# SFT_MainBoard1_0v.net
KiCad netlist of a schematic drawn in EAGLE
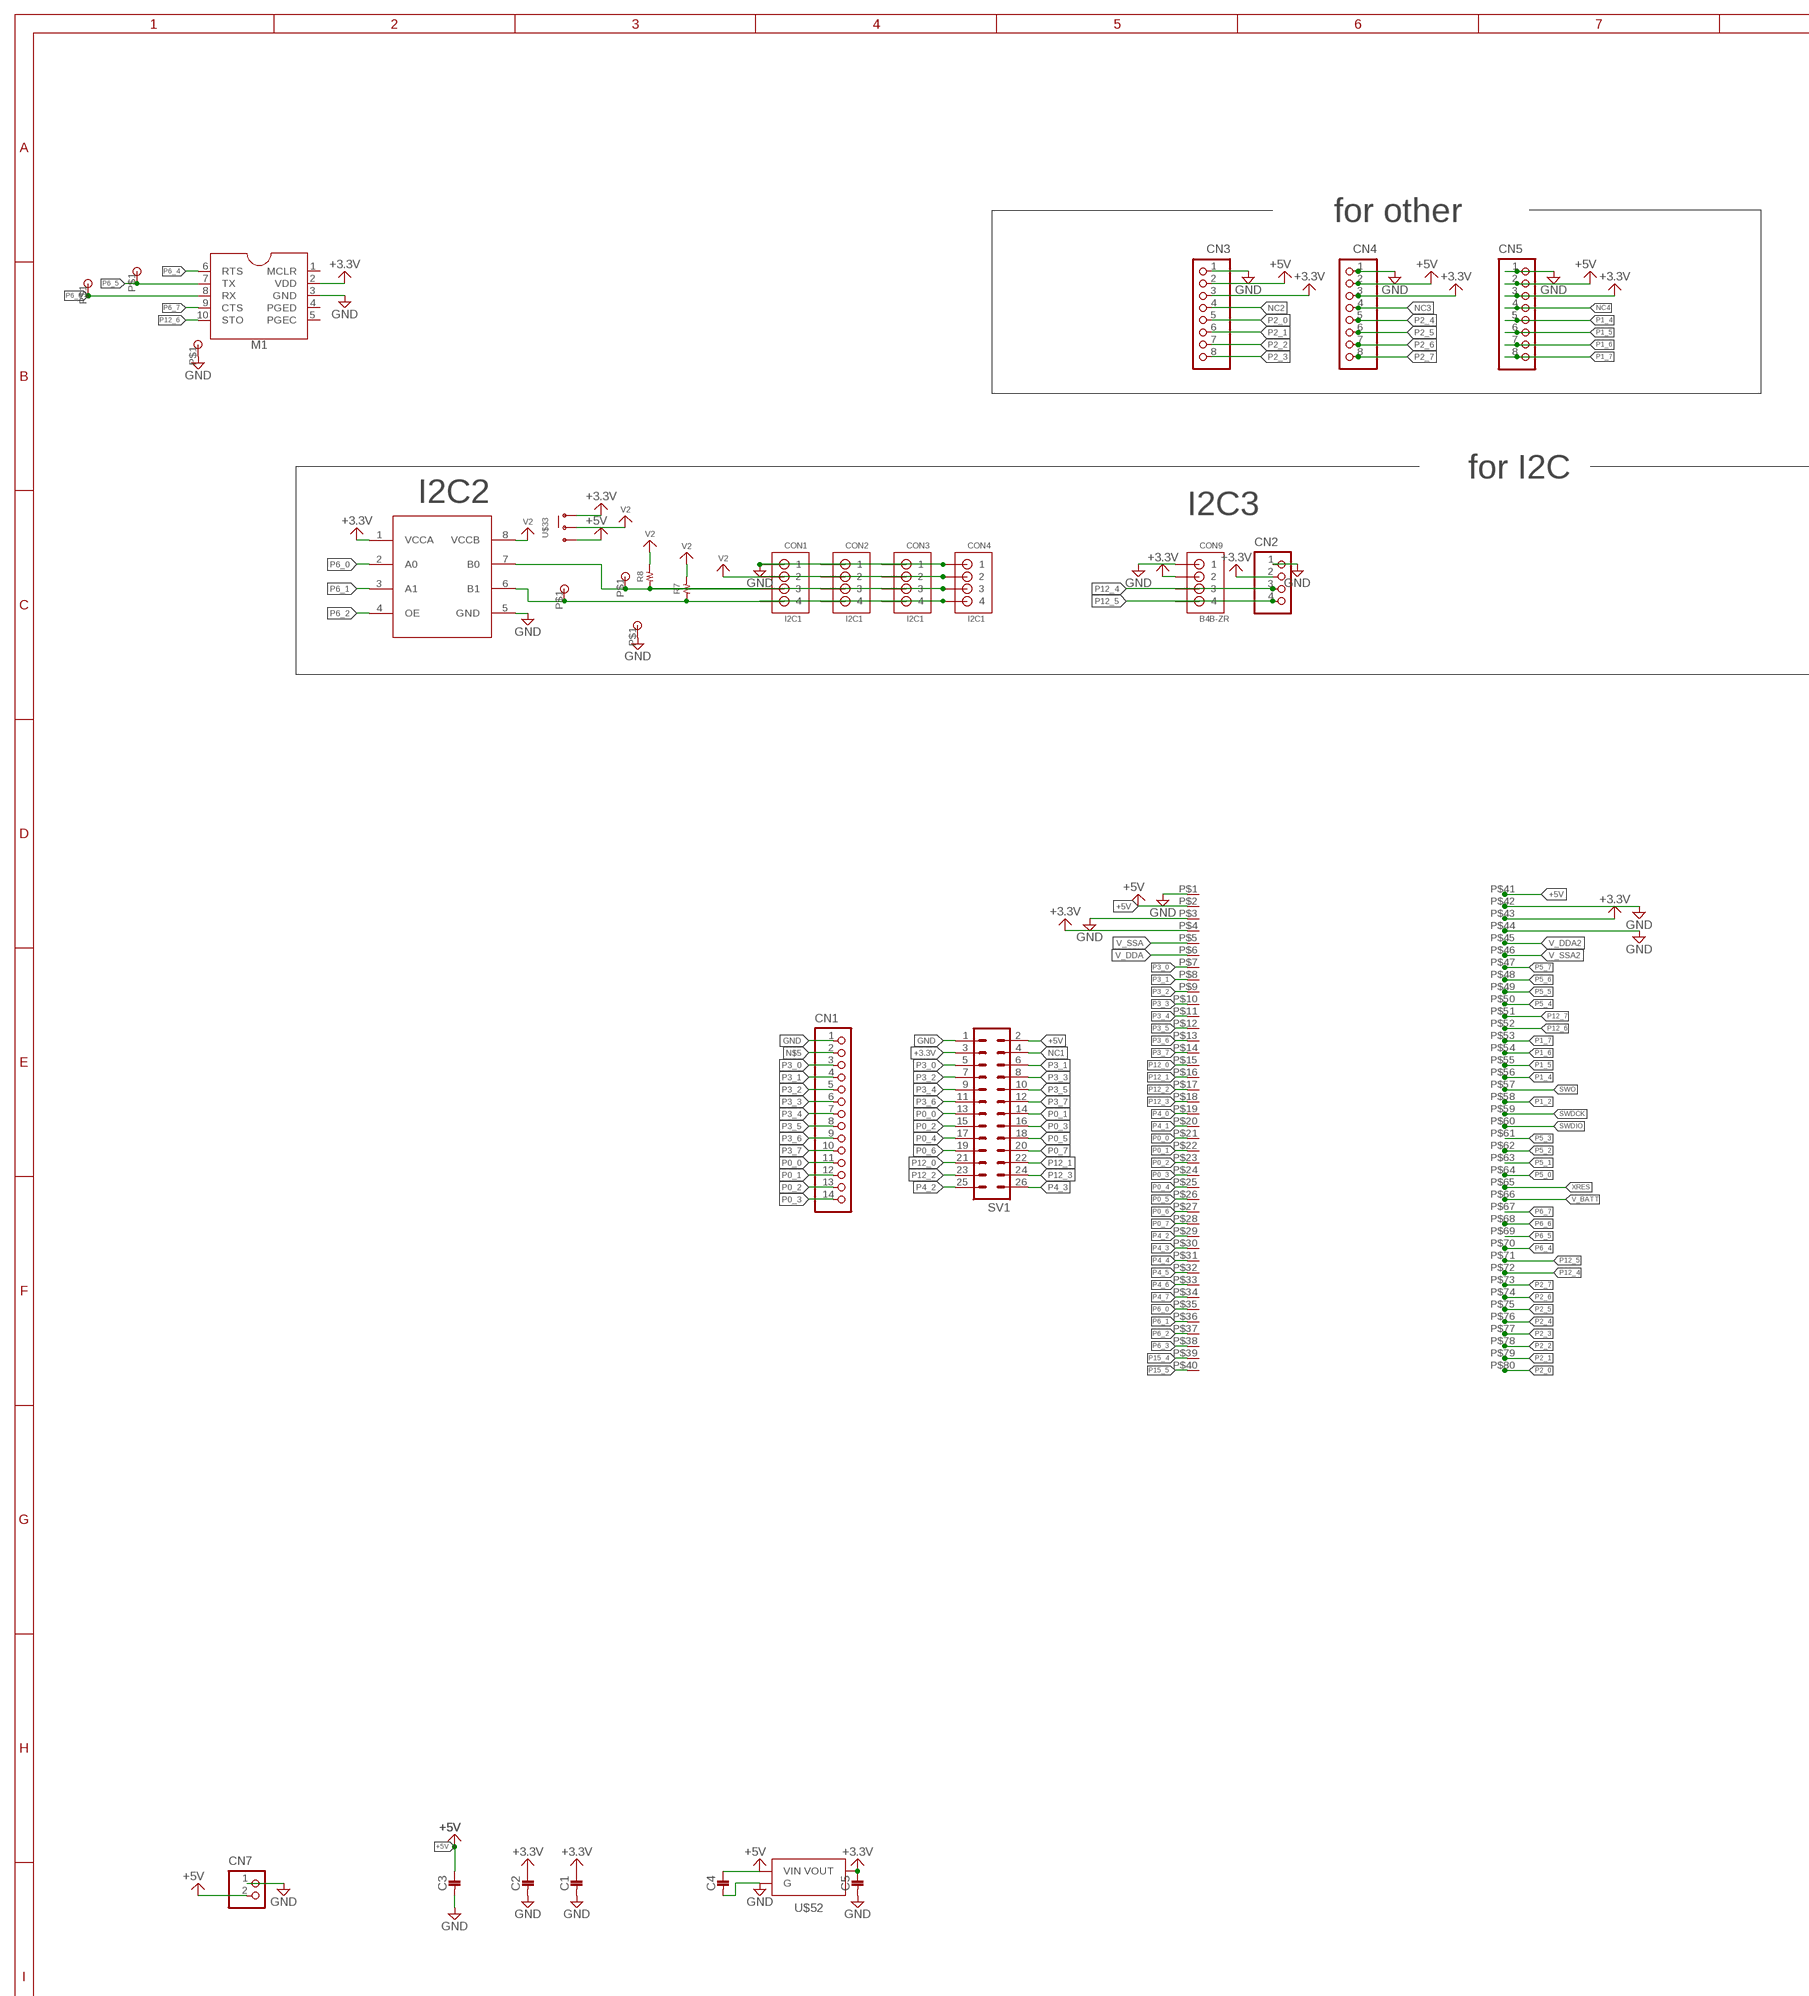
[diagram p0: schematic, sheet 1, part 1 of 2]
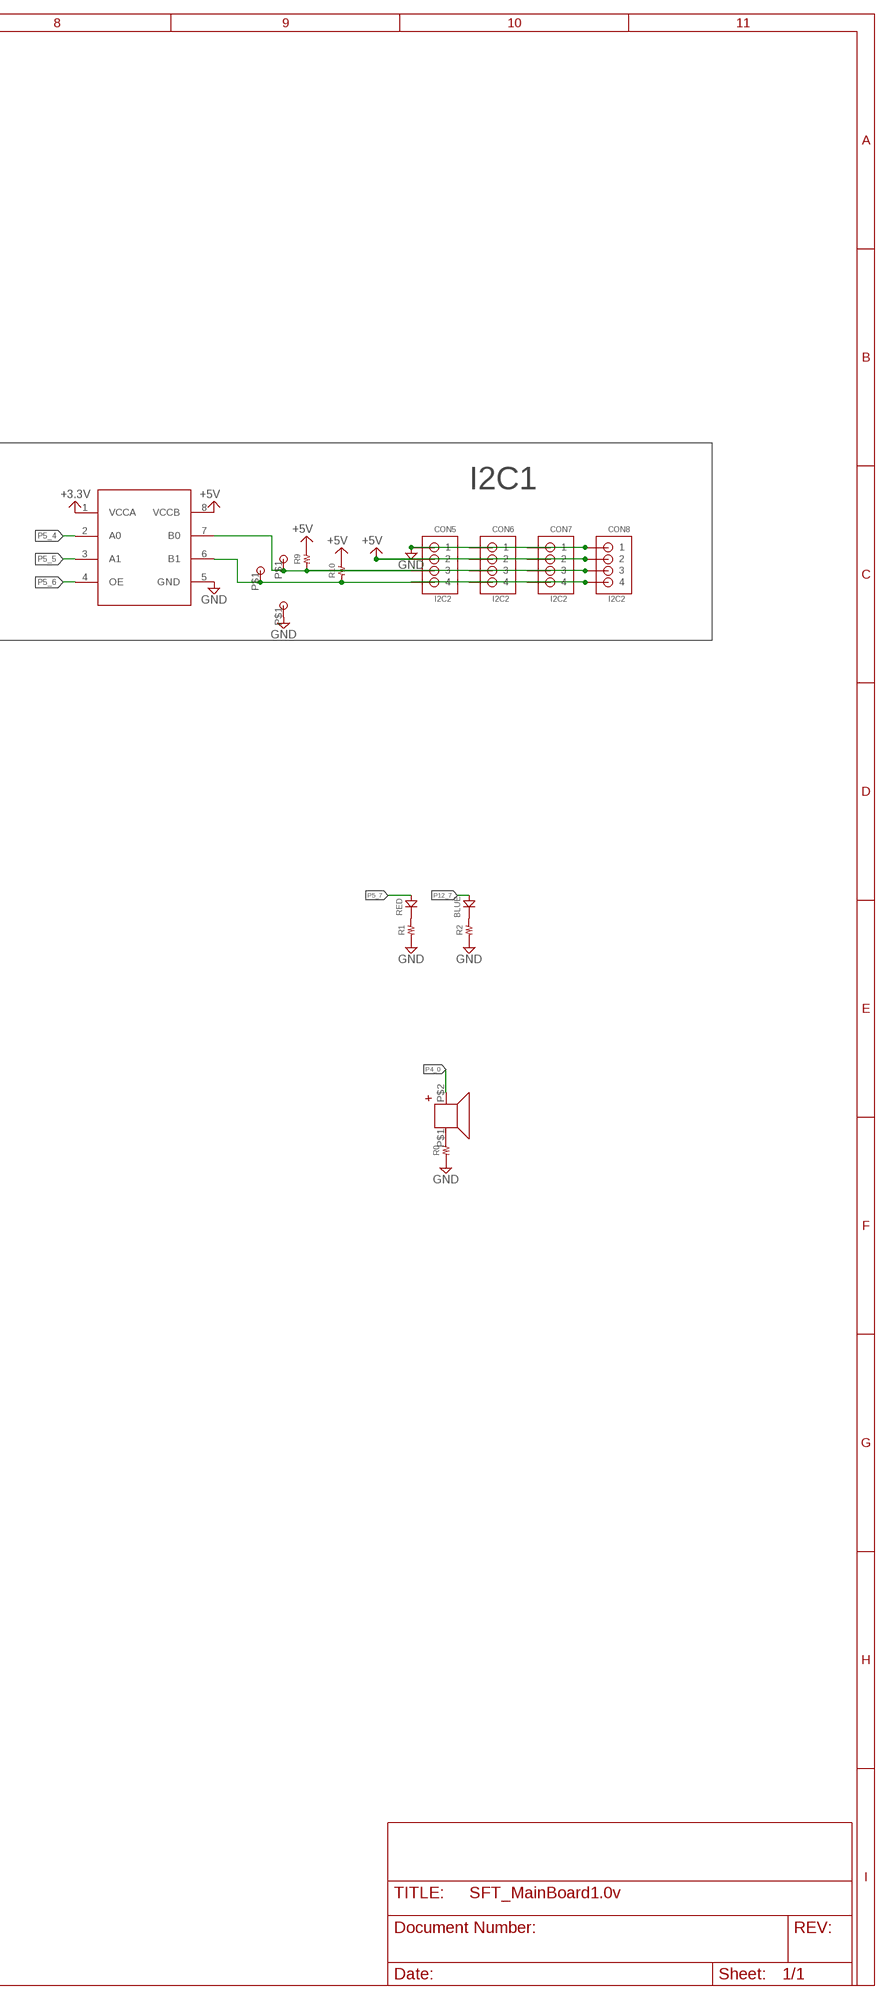
[diagram p1: schematic, sheet 1, part 2 of 2]

(export (version "E")
  (design (tool "Eeschema 10.0.6"))
  (components
    (comp (ref "BLUE")
      (value "CHIPLED")
      (footprint "eagle-import:1608")
      (libsource (lib "eagle-import") (part "CHIPLED"))
    )
    (comp (ref "C1")
      (value "1608")
      (footprint "eagle-import:1608")
      (libsource (lib "eagle-import") (part "1608"))
    )
    (comp (ref "C2")
      (value "1608")
      (footprint "eagle-import:1608")
      (libsource (lib "eagle-import") (part "1608"))
    )
    (comp (ref "C3")
      (value "1608")
      (footprint "eagle-import:1608")
      (libsource (lib "eagle-import") (part "1608"))
    )
    (comp (ref "C4")
      (value "1608")
      (footprint "eagle-import:1608")
      (libsource (lib "eagle-import") (part "1608"))
    )
    (comp (ref "C5")
      (value "1608")
      (footprint "eagle-import:1608")
      (libsource (lib "eagle-import") (part "1608"))
    )
    (comp (ref "CN1")
      (value "B14B-XASK-1")
      (footprint "eagle-import:B14B-XASK-1")
      (libsource (lib "eagle-import") (part "B14B-XASK-1"))
    )
    (comp (ref "CN2")
      (value "B4B-PH-K-S")
      (footprint "eagle-import:B4B-PH-K-S")
      (libsource (lib "eagle-import") (part "B4B-PH-K-S"))
    )
    (comp (ref "CN3")
      (value "B8B-PH-K-S")
      (footprint "eagle-import:B8B-PH-K-S")
      (libsource (lib "eagle-import") (part "B8B-PH-K-S"))
    )
    (comp (ref "CN4")
      (value "B8B-PH-K-S")
      (footprint "eagle-import:B8B-PH-K-S")
      (libsource (lib "eagle-import") (part "B8B-PH-K-S"))
    )
    (comp (ref "CN5")
      (value "B8B-PH-K-S")
      (footprint "eagle-import:B8B-PH-K-S")
      (libsource (lib "eagle-import") (part "B8B-PH-K-S"))
    )
    (comp (ref "CN7")
      (value "B2B-PH-K-S")
      (footprint "eagle-import:B2B-PH-K-S")
      (libsource (lib "eagle-import") (part "B2B-PH-K-S"))
    )
    (comp (ref "CON1")
      (value "I2C1")
      (footprint "eagle-import:B4B-ZR")
      (libsource (lib "eagle-import") (part "B4B-ZR"))
    )
    (comp (ref "CON2")
      (value "I2C1")
      (footprint "eagle-import:B4B-ZR")
      (libsource (lib "eagle-import") (part "B4B-ZR"))
    )
    (comp (ref "CON3")
      (value "I2C1")
      (footprint "eagle-import:B4B-ZR")
      (libsource (lib "eagle-import") (part "B4B-ZR"))
    )
    (comp (ref "CON4")
      (value "I2C1")
      (footprint "eagle-import:B4B-ZR")
      (libsource (lib "eagle-import") (part "B4B-ZR"))
    )
    (comp (ref "CON5")
      (value "I2C2")
      (footprint "eagle-import:B4B-ZR")
      (libsource (lib "eagle-import") (part "B4B-ZR"))
    )
    (comp (ref "CON6")
      (value "I2C2")
      (footprint "eagle-import:B4B-ZR")
      (libsource (lib "eagle-import") (part "B4B-ZR"))
    )
    (comp (ref "CON7")
      (value "I2C2")
      (footprint "eagle-import:B4B-ZR")
      (libsource (lib "eagle-import") (part "B4B-ZR"))
    )
    (comp (ref "CON8")
      (value "I2C2")
      (footprint "eagle-import:B4B-ZR")
      (libsource (lib "eagle-import") (part "B4B-ZR"))
    )
    (comp (ref "CON9")
      (value "B4B-ZR")
      (footprint "eagle-import:B4B-ZR")
      (libsource (lib "eagle-import") (part "B4B-ZR"))
    )
    (comp (ref "IC1")
      (value "I2C_FXMA2102")
      (footprint "eagle-import:DIL08")
      (libsource (lib "eagle-import") (part "I2C_FXMA2102"))
    )
    (comp (ref "IC2")
      (value "I2C_FXMA2102")
      (footprint "eagle-import:DIL08")
      (libsource (lib "eagle-import") (part "I2C_FXMA2102"))
    )
    (comp (ref "M1")
      (value "SBDBT")
      (footprint "eagle-import:DIL10")
      (libsource (lib "eagle-import") (part "SBDBT"))
    )
    (comp (ref "R0")
      (value "RESISTOR__SMD")
      (footprint "eagle-import:1608")
      (libsource (lib "eagle-import") (part "RESISTOR__SMD"))
    )
    (comp (ref "R1")
      (value "RESISTOR__SMD")
      (footprint "eagle-import:1608")
      (libsource (lib "eagle-import") (part "RESISTOR__SMD"))
    )
    (comp (ref "R2")
      (value "RESISTOR__SMD")
      (footprint "eagle-import:1608")
      (libsource (lib "eagle-import") (part "RESISTOR__SMD"))
    )
    (comp (ref "R7")
      (value "RESISTOR__SMD")
      (footprint "eagle-import:1608")
      (libsource (lib "eagle-import") (part "RESISTOR__SMD"))
    )
    (comp (ref "R8")
      (value "RESISTOR__SMD")
      (footprint "eagle-import:1608")
      (libsource (lib "eagle-import") (part "RESISTOR__SMD"))
    )
    (comp (ref "R9")
      (value "RESISTOR__SMD")
      (footprint "eagle-import:1608")
      (libsource (lib "eagle-import") (part "RESISTOR__SMD"))
    )
    (comp (ref "R10")
      (value "RESISTOR__SMD")
      (footprint "eagle-import:1608")
      (libsource (lib "eagle-import") (part "RESISTOR__SMD"))
    )
    (comp (ref "RED")
      (value "CHIPLED")
      (footprint "eagle-import:1608")
      (libsource (lib "eagle-import") (part "CHIPLED"))
    )
    (comp (ref "SP")
      (value "PKLCS1212E4001")
      (footprint "eagle-import:PKLCS1212E4001")
      (libsource (lib "eagle-import") (part "PKLCS1212E4001"))
    )
    (comp (ref "SV1")
      (value "ML26")
      (footprint "eagle-import:ML26")
      (libsource (lib "eagle-import") (part "ML26"))
    )
    (comp (ref "U$2")
      (value "PSOC_5LP")
      (footprint "eagle-import:PSOC_5LP")
      (libsource (lib "eagle-import") (part "PSOC_5LP"))
    )
    (comp (ref "U$15")
      (value "CHECK_0.8MM")
      (footprint "eagle-import:CHECK_0.8MM")
      (libsource (lib "eagle-import") (part "CHECK_0.8MM"))
    )
    (comp (ref "U$18")
      (value "CHECK_0.8MM")
      (footprint "eagle-import:CHECK_0.8MM")
      (libsource (lib "eagle-import") (part "CHECK_0.8MM"))
    )
    (comp (ref "U$33")
      (value "SS12D01G4")
      (footprint "eagle-import:SS12D01G4")
      (libsource (lib "eagle-import") (part "SS12D01G4"))
    )
    (comp (ref "U$37")
      (value "CHECK_0.8MM")
      (footprint "eagle-import:CHECK_0.8MM")
      (libsource (lib "eagle-import") (part "CHECK_0.8MM"))
    )
    (comp (ref "U$38")
      (value "CHECK_0.8MM")
      (footprint "eagle-import:CHECK_0.8MM")
      (libsource (lib "eagle-import") (part "CHECK_0.8MM"))
    )
    (comp (ref "U$39")
      (value "CHECK_0.8MM")
      (footprint "eagle-import:CHECK_0.8MM")
      (libsource (lib "eagle-import") (part "CHECK_0.8MM"))
    )
    (comp (ref "U$52")
      (value "NJM2845")
      (footprint "eagle-import:TO252")
      (libsource (lib "eagle-import") (part "NJM2845"))
    )
    (comp (ref "U$78")
      (value "CHECK_0.8MM")
      (footprint "eagle-import:CHECK_0.8MM")
      (libsource (lib "eagle-import") (part "CHECK_0.8MM"))
    )
    (comp (ref "U$79")
      (value "CHECK_0.8MM")
      (footprint "eagle-import:CHECK_0.8MM")
      (libsource (lib "eagle-import") (part "CHECK_0.8MM"))
    )
    (comp (ref "U$82")
      (value "CHECK_0.8MM")
      (footprint "eagle-import:CHECK_0.8MM")
      (libsource (lib "eagle-import") (part "CHECK_0.8MM"))
    )
    (comp (ref "U$83")
      (value "CHECK_0.8MM")
      (footprint "eagle-import:CHECK_0.8MM")
      (libsource (lib "eagle-import") (part "CHECK_0.8MM"))
    )
  )
  (nets
    (net (code "1") (name "+3.3V") (class "Default")
      (node (ref "C1") (pin "P$1") (pinfunction "1_P$1") (pintype "passive"))
      (node (ref "C2") (pin "P$1") (pinfunction "1_P$1") (pintype "passive"))
      (node (ref "C5") (pin "P$1") (pinfunction "1_P$1") (pintype "passive"))
      (node (ref "CN2") (pin "2") (pinfunction "2_2") (pintype "passive"))
      (node (ref "CN3") (pin "3") (pinfunction "3_3") (pintype "passive"))
      (node (ref "CN4") (pin "3") (pinfunction "3_3") (pintype "passive"))
      (node (ref "CN5") (pin "3") (pinfunction "3_3") (pintype "passive"))
      (node (ref "CON9") (pin "2") (pinfunction "2_2") (pintype "bidirectional"))
      (node (ref "IC1") (pin "1") (pinfunction "VCCA_1") (pintype "bidirectional"))
      (node (ref "IC2") (pin "1") (pinfunction "VCCA_1") (pintype "bidirectional"))
      (node (ref "M1") (pin "2") (pinfunction "VDD_2") (pintype "passive"))
      (node (ref "SV1") (pin "3") (pinfunction "3_3") (pintype "passive"))
      (node (ref "U$2") (pin "P$4") (pinfunction "P$4_P$4") (pintype "bidirectional"))
      (node (ref "U$2") (pin "P$43") (pinfunction "P$43_P$43") (pintype "bidirectional"))
      (node (ref "U$33") (pin "1") (pinfunction "P$1_1") (pintype "bidirectional"))
      (node (ref "U$52") (pin "3") (pinfunction "VOUT_3") (pintype "power_in"))
    )
    (net (code "2") (name "+5V") (class "Default")
      (node (ref "C3") (pin "P$1") (pinfunction "1_P$1") (pintype "passive"))
      (node (ref "C4") (pin "P$1") (pinfunction "1_P$1") (pintype "passive"))
      (node (ref "CN3") (pin "2") (pinfunction "2_2") (pintype "passive"))
      (node (ref "CN4") (pin "2") (pinfunction "2_2") (pintype "passive"))
      (node (ref "CN5") (pin "2") (pinfunction "2_2") (pintype "passive"))
      (node (ref "CN7") (pin "2") (pinfunction "2_2") (pintype "passive"))
      (node (ref "CON5") (pin "2") (pinfunction "2_2") (pintype "bidirectional"))
      (node (ref "CON6") (pin "2") (pinfunction "2_2") (pintype "bidirectional"))
      (node (ref "CON7") (pin "2") (pinfunction "2_2") (pintype "bidirectional"))
      (node (ref "CON8") (pin "2") (pinfunction "2_2") (pintype "bidirectional"))
      (node (ref "IC1") (pin "8") (pinfunction "VCCB_8") (pintype "bidirectional"))
      (node (ref "R10") (pin "2") (pinfunction "P$2_2") (pintype "passive"))
      (node (ref "R9") (pin "2") (pinfunction "P$2_2") (pintype "passive"))
      (node (ref "SV1") (pin "2") (pinfunction "2_2") (pintype "passive"))
      (node (ref "U$2") (pin "P$2") (pinfunction "P$2_P$2") (pintype "bidirectional"))
      (node (ref "U$2") (pin "P$41") (pinfunction "P$41_P$41") (pintype "bidirectional"))
      (node (ref "U$33") (pin "3") (pinfunction "P$3_3") (pintype "bidirectional"))
      (node (ref "U$52") (pin "1") (pinfunction "VIN_1") (pintype "power_in"))
    )
    (net (code "3") (name "GND") (class "Default")
      (node (ref "C1") (pin "P$2") (pinfunction "2_P$2") (pintype "passive"))
      (node (ref "C2") (pin "P$2") (pinfunction "2_P$2") (pintype "passive"))
      (node (ref "C3") (pin "P$2") (pinfunction "2_P$2") (pintype "passive"))
      (node (ref "C4") (pin "P$2") (pinfunction "2_P$2") (pintype "passive"))
      (node (ref "C5") (pin "P$2") (pinfunction "2_P$2") (pintype "passive"))
      (node (ref "CN1") (pin "1") (pinfunction "1_1") (pintype "passive"))
      (node (ref "CN2") (pin "1") (pinfunction "1_1") (pintype "passive"))
      (node (ref "CN3") (pin "1") (pinfunction "1_1") (pintype "passive"))
      (node (ref "CN4") (pin "1") (pinfunction "1_1") (pintype "passive"))
      (node (ref "CN5") (pin "1") (pinfunction "1_1") (pintype "passive"))
      (node (ref "CN7") (pin "1") (pinfunction "1_1") (pintype "passive"))
      (node (ref "CON1") (pin "1") (pinfunction "1_1") (pintype "bidirectional"))
      (node (ref "CON2") (pin "1") (pinfunction "1_1") (pintype "bidirectional"))
      (node (ref "CON3") (pin "1") (pinfunction "1_1") (pintype "bidirectional"))
      (node (ref "CON4") (pin "1") (pinfunction "1_1") (pintype "bidirectional"))
      (node (ref "CON5") (pin "1") (pinfunction "1_1") (pintype "bidirectional"))
      (node (ref "CON6") (pin "1") (pinfunction "1_1") (pintype "bidirectional"))
      (node (ref "CON7") (pin "1") (pinfunction "1_1") (pintype "bidirectional"))
      (node (ref "CON8") (pin "1") (pinfunction "1_1") (pintype "bidirectional"))
      (node (ref "CON9") (pin "1") (pinfunction "1_1") (pintype "bidirectional"))
      (node (ref "IC1") (pin "5") (pinfunction "GND_5") (pintype "bidirectional"))
      (node (ref "IC2") (pin "5") (pinfunction "GND_5") (pintype "bidirectional"))
      (node (ref "M1") (pin "3") (pinfunction "GND_3") (pintype "passive"))
      (node (ref "R0") (pin "1") (pinfunction "P$1_1") (pintype "passive"))
      (node (ref "R1") (pin "1") (pinfunction "P$1_1") (pintype "passive"))
      (node (ref "R2") (pin "1") (pinfunction "P$1_1") (pintype "passive"))
      (node (ref "SV1") (pin "1") (pinfunction "1_1") (pintype "passive"))
      (node (ref "U$2") (pin "P$1") (pinfunction "P$1_P$1") (pintype "bidirectional"))
      (node (ref "U$2") (pin "P$3") (pinfunction "P$3_P$3") (pintype "bidirectional"))
      (node (ref "U$2") (pin "P$42") (pinfunction "P$42_P$42") (pintype "bidirectional"))
      (node (ref "U$2") (pin "P$44") (pinfunction "P$44_P$44") (pintype "bidirectional"))
      (node (ref "U$37") (pin "P$1") (pinfunction "P$1_P$1") (pintype "bidirectional"))
      (node (ref "U$38") (pin "P$1") (pinfunction "P$1_P$1") (pintype "bidirectional"))
      (node (ref "U$39") (pin "P$1") (pinfunction "P$1_P$1") (pintype "bidirectional"))
      (node (ref "U$52") (pin "2") (pinfunction "G_2") (pintype "power_in"))
    )
    (net (code "4") (name "N$5") (class "Default")
      (node (ref "CN1") (pin "2") (pinfunction "2_2") (pintype "passive"))
    )
    (net (code "5") (name "NC1") (class "Default")
      (node (ref "SV1") (pin "4") (pinfunction "4_4") (pintype "passive"))
    )
    (net (code "6") (name "NC2") (class "Default")
      (node (ref "CN3") (pin "4") (pinfunction "4_4") (pintype "passive"))
    )
    (net (code "7") (name "NC3") (class "Default")
      (node (ref "CN4") (pin "4") (pinfunction "4_4") (pintype "passive"))
    )
    (net (code "8") (name "NC4") (class "Default")
      (node (ref "CN5") (pin "4") (pinfunction "4_4") (pintype "passive"))
    )
    (net (code "9") (name "Net-(BLUE-K)") (class "Default")
      (node (ref "BLUE") (pin "2") (pinfunction "K_2") (pintype "bidirectional"))
      (node (ref "R2") (pin "2") (pinfunction "P$2_2") (pintype "passive"))
    )
    (net (code "10") (name "Net-(IC1-B0)") (class "Default")
      (node (ref "CON5") (pin "3") (pinfunction "3_3") (pintype "bidirectional"))
      (node (ref "CON6") (pin "3") (pinfunction "3_3") (pintype "bidirectional"))
      (node (ref "CON7") (pin "3") (pinfunction "3_3") (pintype "bidirectional"))
      (node (ref "CON8") (pin "3") (pinfunction "3_3") (pintype "bidirectional"))
      (node (ref "IC1") (pin "7") (pinfunction "B0_7") (pintype "bidirectional"))
      (node (ref "R9") (pin "1") (pinfunction "P$1_1") (pintype "passive"))
      (node (ref "U$18") (pin "P$1") (pinfunction "P$1_P$1") (pintype "bidirectional"))
    )
    (net (code "11") (name "Net-(IC1-B1)") (class "Default")
      (node (ref "CON5") (pin "4") (pinfunction "4_4") (pintype "bidirectional"))
      (node (ref "CON6") (pin "4") (pinfunction "4_4") (pintype "bidirectional"))
      (node (ref "CON7") (pin "4") (pinfunction "4_4") (pintype "bidirectional"))
      (node (ref "CON8") (pin "4") (pinfunction "4_4") (pintype "bidirectional"))
      (node (ref "IC1") (pin "6") (pinfunction "B1_6") (pintype "bidirectional"))
      (node (ref "R10") (pin "1") (pinfunction "P$1_1") (pintype "passive"))
      (node (ref "U$15") (pin "P$1") (pinfunction "P$1_P$1") (pintype "bidirectional"))
    )
    (net (code "12") (name "Net-(IC2-B0)") (class "Default")
      (node (ref "CON1") (pin "3") (pinfunction "3_3") (pintype "bidirectional"))
      (node (ref "CON2") (pin "3") (pinfunction "3_3") (pintype "bidirectional"))
      (node (ref "CON3") (pin "3") (pinfunction "3_3") (pintype "bidirectional"))
      (node (ref "CON4") (pin "3") (pinfunction "3_3") (pintype "bidirectional"))
      (node (ref "IC2") (pin "7") (pinfunction "B0_7") (pintype "bidirectional"))
      (node (ref "R8") (pin "1") (pinfunction "P$1_1") (pintype "passive"))
      (node (ref "U$79") (pin "P$1") (pinfunction "P$1_P$1") (pintype "bidirectional"))
    )
    (net (code "13") (name "Net-(IC2-B1)") (class "Default")
      (node (ref "CON1") (pin "4") (pinfunction "4_4") (pintype "bidirectional"))
      (node (ref "CON2") (pin "4") (pinfunction "4_4") (pintype "bidirectional"))
      (node (ref "CON3") (pin "4") (pinfunction "4_4") (pintype "bidirectional"))
      (node (ref "CON4") (pin "4") (pinfunction "4_4") (pintype "bidirectional"))
      (node (ref "IC2") (pin "6") (pinfunction "B1_6") (pintype "bidirectional"))
      (node (ref "R7") (pin "1") (pinfunction "P$1_1") (pintype "passive"))
      (node (ref "U$78") (pin "P$1") (pinfunction "P$1_P$1") (pintype "bidirectional"))
    )
    (net (code "14") (name "Net-(R0-P$2)") (class "Default")
      (node (ref "R0") (pin "2") (pinfunction "P$2_2") (pintype "passive"))
      (node (ref "SP") (pin "P$1") (pinfunction "MINUS_P$1") (pintype "bidirectional"))
    )
    (net (code "15") (name "Net-(R1-P$2)") (class "Default")
      (node (ref "R1") (pin "2") (pinfunction "P$2_2") (pintype "passive"))
      (node (ref "RED") (pin "2") (pinfunction "K_2") (pintype "bidirectional"))
    )
    (net (code "16") (name "P0_0") (class "Default")
      (node (ref "CN1") (pin "11") (pinfunction "11_11") (pintype "passive"))
      (node (ref "SV1") (pin "13") (pinfunction "13_13") (pintype "passive"))
      (node (ref "U$2") (pin "P$21") (pinfunction "P$21_P$21") (pintype "bidirectional"))
    )
    (net (code "17") (name "P0_1") (class "Default")
      (node (ref "CN1") (pin "12") (pinfunction "12_12") (pintype "passive"))
      (node (ref "SV1") (pin "14") (pinfunction "14_14") (pintype "passive"))
      (node (ref "U$2") (pin "P$22") (pinfunction "P$22_P$22") (pintype "bidirectional"))
    )
    (net (code "18") (name "P0_2") (class "Default")
      (node (ref "CN1") (pin "13") (pinfunction "13_13") (pintype "passive"))
      (node (ref "SV1") (pin "15") (pinfunction "15_15") (pintype "passive"))
      (node (ref "U$2") (pin "P$23") (pinfunction "P$23_P$23") (pintype "bidirectional"))
    )
    (net (code "19") (name "P0_3") (class "Default")
      (node (ref "CN1") (pin "14") (pinfunction "14_14") (pintype "passive"))
      (node (ref "SV1") (pin "16") (pinfunction "16_16") (pintype "passive"))
      (node (ref "U$2") (pin "P$24") (pinfunction "P$24_P$24") (pintype "bidirectional"))
    )
    (net (code "20") (name "P0_4") (class "Default")
      (node (ref "SV1") (pin "17") (pinfunction "17_17") (pintype "passive"))
      (node (ref "U$2") (pin "P$25") (pinfunction "P$25_P$25") (pintype "bidirectional"))
    )
    (net (code "21") (name "P0_5") (class "Default")
      (node (ref "SV1") (pin "18") (pinfunction "18_18") (pintype "passive"))
      (node (ref "U$2") (pin "P$26") (pinfunction "P$26_P$26") (pintype "bidirectional"))
    )
    (net (code "22") (name "P0_6") (class "Default")
      (node (ref "SV1") (pin "19") (pinfunction "19_19") (pintype "passive"))
      (node (ref "U$2") (pin "P$27") (pinfunction "P$27_P$27") (pintype "bidirectional"))
    )
    (net (code "23") (name "P0_7") (class "Default")
      (node (ref "SV1") (pin "20") (pinfunction "20_20") (pintype "passive"))
      (node (ref "U$2") (pin "P$28") (pinfunction "P$28_P$28") (pintype "bidirectional"))
    )
    (net (code "24") (name "P1_2") (class "Default")
      (node (ref "U$2") (pin "P$58") (pinfunction "P$58_P$58") (pintype "bidirectional"))
    )
    (net (code "25") (name "P1_4") (class "Default")
      (node (ref "CN5") (pin "5") (pinfunction "5_5") (pintype "passive"))
      (node (ref "U$2") (pin "P$56") (pinfunction "P$56_P$56") (pintype "bidirectional"))
    )
    (net (code "26") (name "P1_5") (class "Default")
      (node (ref "CN5") (pin "6") (pinfunction "6_6") (pintype "passive"))
      (node (ref "U$2") (pin "P$55") (pinfunction "P$55_P$55") (pintype "bidirectional"))
    )
    (net (code "27") (name "P1_6") (class "Default")
      (node (ref "CN5") (pin "7") (pinfunction "7_7") (pintype "passive"))
      (node (ref "U$2") (pin "P$54") (pinfunction "P$54_P$54") (pintype "bidirectional"))
    )
    (net (code "28") (name "P1_7") (class "Default")
      (node (ref "CN5") (pin "8") (pinfunction "8_8") (pintype "passive"))
      (node (ref "U$2") (pin "P$53") (pinfunction "P$53_P$53") (pintype "bidirectional"))
    )
    (net (code "29") (name "P2_0") (class "Default")
      (node (ref "CN3") (pin "5") (pinfunction "5_5") (pintype "passive"))
      (node (ref "U$2") (pin "P$80") (pinfunction "P$80_P$80") (pintype "bidirectional"))
    )
    (net (code "30") (name "P2_1") (class "Default")
      (node (ref "CN3") (pin "6") (pinfunction "6_6") (pintype "passive"))
      (node (ref "U$2") (pin "P$79") (pinfunction "P$79_P$79") (pintype "bidirectional"))
    )
    (net (code "31") (name "P2_2") (class "Default")
      (node (ref "CN3") (pin "7") (pinfunction "7_7") (pintype "passive"))
      (node (ref "U$2") (pin "P$78") (pinfunction "P$78_P$78") (pintype "bidirectional"))
    )
    (net (code "32") (name "P2_3") (class "Default")
      (node (ref "CN3") (pin "8") (pinfunction "8_8") (pintype "passive"))
      (node (ref "U$2") (pin "P$77") (pinfunction "P$77_P$77") (pintype "bidirectional"))
    )
    (net (code "33") (name "P2_4") (class "Default")
      (node (ref "CN4") (pin "5") (pinfunction "5_5") (pintype "passive"))
      (node (ref "U$2") (pin "P$76") (pinfunction "P$76_P$76") (pintype "bidirectional"))
    )
    (net (code "34") (name "P2_5") (class "Default")
      (node (ref "CN4") (pin "6") (pinfunction "6_6") (pintype "passive"))
      (node (ref "U$2") (pin "P$75") (pinfunction "P$75_P$75") (pintype "bidirectional"))
    )
    (net (code "35") (name "P2_6") (class "Default")
      (node (ref "CN4") (pin "7") (pinfunction "7_7") (pintype "passive"))
      (node (ref "U$2") (pin "P$74") (pinfunction "P$74_P$74") (pintype "bidirectional"))
    )
    (net (code "36") (name "P2_7") (class "Default")
      (node (ref "CN4") (pin "8") (pinfunction "8_8") (pintype "passive"))
      (node (ref "U$2") (pin "P$73") (pinfunction "P$73_P$73") (pintype "bidirectional"))
    )
    (net (code "37") (name "P3_0") (class "Default")
      (node (ref "CN1") (pin "3") (pinfunction "3_3") (pintype "passive"))
      (node (ref "SV1") (pin "5") (pinfunction "5_5") (pintype "passive"))
      (node (ref "U$2") (pin "P$7") (pinfunction "P$7_P$7") (pintype "bidirectional"))
    )
    (net (code "38") (name "P3_1") (class "Default")
      (node (ref "CN1") (pin "4") (pinfunction "4_4") (pintype "passive"))
      (node (ref "SV1") (pin "6") (pinfunction "6_6") (pintype "passive"))
      (node (ref "U$2") (pin "P$8") (pinfunction "P$8_P$8") (pintype "bidirectional"))
    )
    (net (code "39") (name "P3_2") (class "Default")
      (node (ref "CN1") (pin "5") (pinfunction "5_5") (pintype "passive"))
      (node (ref "SV1") (pin "7") (pinfunction "7_7") (pintype "passive"))
      (node (ref "U$2") (pin "P$9") (pinfunction "P$9_P$9") (pintype "bidirectional"))
    )
    (net (code "40") (name "P3_3") (class "Default")
      (node (ref "CN1") (pin "6") (pinfunction "6_6") (pintype "passive"))
      (node (ref "SV1") (pin "8") (pinfunction "8_8") (pintype "passive"))
      (node (ref "U$2") (pin "P$10") (pinfunction "P$10_P$10") (pintype "bidirectional"))
    )
    (net (code "41") (name "P3_4") (class "Default")
      (node (ref "CN1") (pin "7") (pinfunction "7_7") (pintype "passive"))
      (node (ref "SV1") (pin "9") (pinfunction "9_9") (pintype "passive"))
      (node (ref "U$2") (pin "P$11") (pinfunction "P$11_P$11") (pintype "bidirectional"))
    )
    (net (code "42") (name "P3_5") (class "Default")
      (node (ref "CN1") (pin "8") (pinfunction "8_8") (pintype "passive"))
      (node (ref "SV1") (pin "10") (pinfunction "10_10") (pintype "passive"))
      (node (ref "U$2") (pin "P$12") (pinfunction "P$12_P$12") (pintype "bidirectional"))
    )
    (net (code "43") (name "P3_6") (class "Default")
      (node (ref "CN1") (pin "9") (pinfunction "9_9") (pintype "passive"))
      (node (ref "SV1") (pin "11") (pinfunction "11_11") (pintype "passive"))
      (node (ref "U$2") (pin "P$13") (pinfunction "P$13_P$13") (pintype "bidirectional"))
    )
    (net (code "44") (name "P3_7") (class "Default")
      (node (ref "CN1") (pin "10") (pinfunction "10_10") (pintype "passive"))
      (node (ref "SV1") (pin "12") (pinfunction "12_12") (pintype "passive"))
      (node (ref "U$2") (pin "P$14") (pinfunction "P$14_P$14") (pintype "bidirectional"))
    )
    (net (code "45") (name "P4_0") (class "Default")
      (node (ref "SP") (pin "P$2") (pinfunction "PLUS_P$2") (pintype "bidirectional"))
      (node (ref "U$2") (pin "P$19") (pinfunction "P$19_P$19") (pintype "bidirectional"))
    )
    (net (code "46") (name "P4_1") (class "Default")
      (node (ref "U$2") (pin "P$20") (pinfunction "P$20_P$20") (pintype "bidirectional"))
    )
    (net (code "47") (name "P4_2") (class "Default")
      (node (ref "SV1") (pin "25") (pinfunction "25_25") (pintype "passive"))
      (node (ref "U$2") (pin "P$29") (pinfunction "P$29_P$29") (pintype "bidirectional"))
    )
    (net (code "48") (name "P4_3") (class "Default")
      (node (ref "SV1") (pin "26") (pinfunction "26_26") (pintype "passive"))
      (node (ref "U$2") (pin "P$30") (pinfunction "P$30_P$30") (pintype "bidirectional"))
    )
    (net (code "49") (name "P4_4") (class "Default")
      (node (ref "U$2") (pin "P$31") (pinfunction "P$31_P$31") (pintype "bidirectional"))
    )
    (net (code "50") (name "P4_5") (class "Default")
      (node (ref "U$2") (pin "P$32") (pinfunction "P$32_P$32") (pintype "bidirectional"))
    )
    (net (code "51") (name "P4_6") (class "Default")
      (node (ref "U$2") (pin "P$33") (pinfunction "P$33_P$33") (pintype "bidirectional"))
    )
    (net (code "52") (name "P4_7") (class "Default")
      (node (ref "U$2") (pin "P$34") (pinfunction "P$34_P$34") (pintype "bidirectional"))
    )
    (net (code "53") (name "P5_0") (class "Default")
      (node (ref "U$2") (pin "P$64") (pinfunction "P$64_P$64") (pintype "bidirectional"))
    )
    (net (code "54") (name "P5_1") (class "Default")
      (node (ref "U$2") (pin "P$63") (pinfunction "P$63_P$63") (pintype "bidirectional"))
    )
    (net (code "55") (name "P5_2") (class "Default")
      (node (ref "U$2") (pin "P$62") (pinfunction "P$62_P$62") (pintype "bidirectional"))
    )
    (net (code "56") (name "P5_3") (class "Default")
      (node (ref "U$2") (pin "P$61") (pinfunction "P$61_P$61") (pintype "bidirectional"))
    )
    (net (code "57") (name "P5_4") (class "Default")
      (node (ref "IC1") (pin "2") (pinfunction "A0_2") (pintype "bidirectional"))
      (node (ref "U$2") (pin "P$50") (pinfunction "P$50_P$50") (pintype "bidirectional"))
    )
    (net (code "58") (name "P5_5") (class "Default")
      (node (ref "IC1") (pin "3") (pinfunction "A1_3") (pintype "bidirectional"))
      (node (ref "U$2") (pin "P$49") (pinfunction "P$49_P$49") (pintype "bidirectional"))
    )
    (net (code "59") (name "P5_6") (class "Default")
      (node (ref "IC1") (pin "4") (pinfunction "OE_4") (pintype "bidirectional"))
      (node (ref "U$2") (pin "P$48") (pinfunction "P$48_P$48") (pintype "bidirectional"))
    )
    (net (code "60") (name "P5_7") (class "Default")
      (node (ref "RED") (pin "1") (pinfunction "A_1") (pintype "bidirectional"))
      (node (ref "U$2") (pin "P$47") (pinfunction "P$47_P$47") (pintype "bidirectional"))
    )
    (net (code "61") (name "P6_0") (class "Default")
      (node (ref "IC2") (pin "2") (pinfunction "A0_2") (pintype "bidirectional"))
      (node (ref "U$2") (pin "P$35") (pinfunction "P$35_P$35") (pintype "bidirectional"))
    )
    (net (code "62") (name "P6_1") (class "Default")
      (node (ref "IC2") (pin "3") (pinfunction "A1_3") (pintype "bidirectional"))
      (node (ref "U$2") (pin "P$36") (pinfunction "P$36_P$36") (pintype "bidirectional"))
    )
    (net (code "63") (name "P6_2") (class "Default")
      (node (ref "IC2") (pin "4") (pinfunction "OE_4") (pintype "bidirectional"))
      (node (ref "U$2") (pin "P$37") (pinfunction "P$37_P$37") (pintype "bidirectional"))
    )
    (net (code "64") (name "P6_3") (class "Default")
      (node (ref "U$2") (pin "P$38") (pinfunction "P$38_P$38") (pintype "bidirectional"))
    )
    (net (code "65") (name "P6_4") (class "Default")
      (node (ref "M1") (pin "6") (pinfunction "RTS_6") (pintype "passive"))
      (node (ref "U$2") (pin "P$70") (pinfunction "P$70_P$70") (pintype "bidirectional"))
    )
    (net (code "66") (name "P6_5") (class "Default")
      (node (ref "M1") (pin "7") (pinfunction "TX_7") (pintype "passive"))
      (node (ref "U$2") (pin "P$69") (pinfunction "P$69_P$69") (pintype "bidirectional"))
      (node (ref "U$82") (pin "P$1") (pinfunction "P$1_P$1") (pintype "bidirectional"))
    )
    (net (code "67") (name "P6_6") (class "Default")
      (node (ref "M1") (pin "8") (pinfunction "RX_8") (pintype "passive"))
      (node (ref "U$2") (pin "P$68") (pinfunction "P$68_P$68") (pintype "bidirectional"))
      (node (ref "U$83") (pin "P$1") (pinfunction "P$1_P$1") (pintype "bidirectional"))
    )
    (net (code "68") (name "P6_7") (class "Default")
      (node (ref "M1") (pin "9") (pinfunction "CTS_9") (pintype "passive"))
      (node (ref "U$2") (pin "P$67") (pinfunction "P$67_P$67") (pintype "bidirectional"))
    )
    (net (code "69") (name "P12_0") (class "Default")
      (node (ref "SV1") (pin "21") (pinfunction "21_21") (pintype "passive"))
      (node (ref "U$2") (pin "P$15") (pinfunction "P$15_P$15") (pintype "bidirectional"))
    )
    (net (code "70") (name "P12_1") (class "Default")
      (node (ref "SV1") (pin "22") (pinfunction "22_22") (pintype "passive"))
      (node (ref "U$2") (pin "P$16") (pinfunction "P$16_P$16") (pintype "bidirectional"))
    )
    (net (code "71") (name "P12_2") (class "Default")
      (node (ref "SV1") (pin "23") (pinfunction "23_23") (pintype "passive"))
      (node (ref "U$2") (pin "P$17") (pinfunction "P$17_P$17") (pintype "bidirectional"))
    )
    (net (code "72") (name "P12_3") (class "Default")
      (node (ref "SV1") (pin "24") (pinfunction "24_24") (pintype "passive"))
      (node (ref "U$2") (pin "P$18") (pinfunction "P$18_P$18") (pintype "bidirectional"))
    )
    (net (code "73") (name "P12_4") (class "Default")
      (node (ref "CN2") (pin "3") (pinfunction "3_3") (pintype "passive"))
      (node (ref "CON9") (pin "3") (pinfunction "3_3") (pintype "bidirectional"))
      (node (ref "U$2") (pin "P$72") (pinfunction "P$72_P$72") (pintype "bidirectional"))
    )
    (net (code "74") (name "P12_5") (class "Default")
      (node (ref "CN2") (pin "4") (pinfunction "4_4") (pintype "passive"))
      (node (ref "CON9") (pin "4") (pinfunction "4_4") (pintype "bidirectional"))
      (node (ref "U$2") (pin "P$71") (pinfunction "P$71_P$71") (pintype "bidirectional"))
    )
    (net (code "75") (name "P12_6") (class "Default")
      (node (ref "M1") (pin "10") (pinfunction "STO_10") (pintype "passive"))
      (node (ref "U$2") (pin "P$52") (pinfunction "P$52_P$52") (pintype "bidirectional"))
    )
    (net (code "76") (name "P12_7") (class "Default")
      (node (ref "BLUE") (pin "1") (pinfunction "A_1") (pintype "bidirectional"))
      (node (ref "U$2") (pin "P$51") (pinfunction "P$51_P$51") (pintype "bidirectional"))
    )
    (net (code "77") (name "P15_4") (class "Default")
      (node (ref "U$2") (pin "P$39") (pinfunction "P$39_P$39") (pintype "bidirectional"))
    )
    (net (code "78") (name "P15_5") (class "Default")
      (node (ref "U$2") (pin "P$40") (pinfunction "P$40_P$40") (pintype "bidirectional"))
    )
    (net (code "79") (name "SWDCK") (class "Default")
      (node (ref "U$2") (pin "P$59") (pinfunction "P$59_P$59") (pintype "bidirectional"))
    )
    (net (code "80") (name "SWDIO") (class "Default")
      (node (ref "U$2") (pin "P$60") (pinfunction "P$60_P$60") (pintype "bidirectional"))
    )
    (net (code "81") (name "SWO") (class "Default")
      (node (ref "U$2") (pin "P$57") (pinfunction "P$57_P$57") (pintype "bidirectional"))
    )
    (net (code "82") (name "V2") (class "Default")
      (node (ref "CON1") (pin "2") (pinfunction "2_2") (pintype "bidirectional"))
      (node (ref "CON2") (pin "2") (pinfunction "2_2") (pintype "bidirectional"))
      (node (ref "CON3") (pin "2") (pinfunction "2_2") (pintype "bidirectional"))
      (node (ref "CON4") (pin "2") (pinfunction "2_2") (pintype "bidirectional"))
      (node (ref "IC2") (pin "8") (pinfunction "VCCB_8") (pintype "bidirectional"))
      (node (ref "R7") (pin "2") (pinfunction "P$2_2") (pintype "passive"))
      (node (ref "R8") (pin "2") (pinfunction "P$2_2") (pintype "passive"))
      (node (ref "U$33") (pin "2") (pinfunction "P$2_2") (pintype "bidirectional"))
    )
    (net (code "83") (name "V_BATT") (class "Default")
      (node (ref "U$2") (pin "P$66") (pinfunction "P$66_P$66") (pintype "bidirectional"))
    )
    (net (code "84") (name "V_DDA") (class "Default")
      (node (ref "U$2") (pin "P$6") (pinfunction "P$6_P$6") (pintype "bidirectional"))
    )
    (net (code "85") (name "V_DDA2") (class "Default")
      (node (ref "U$2") (pin "P$45") (pinfunction "P$45_P$45") (pintype "bidirectional"))
    )
    (net (code "86") (name "V_SSA") (class "Default")
      (node (ref "U$2") (pin "P$5") (pinfunction "P$5_P$5") (pintype "bidirectional"))
    )
    (net (code "87") (name "V_SSA2") (class "Default")
      (node (ref "U$2") (pin "P$46") (pinfunction "P$46_P$46") (pintype "bidirectional"))
    )
    (net (code "88") (name "XRES") (class "Default")
      (node (ref "U$2") (pin "P$65") (pinfunction "P$65_P$65") (pintype "bidirectional"))
    )
    (net (code "89") (name "unconnected-(M1-MCLR-Pad1)") (class "Default")
      (node (ref "M1") (pin "1") (pinfunction "MCLR_1") (pintype "passive"))
    )
    (net (code "90") (name "unconnected-(M1-PGEC-Pad5)") (class "Default")
      (node (ref "M1") (pin "5") (pinfunction "PGEC_5") (pintype "passive"))
    )
    (net (code "91") (name "unconnected-(M1-PGED-Pad4)") (class "Default")
      (node (ref "M1") (pin "4") (pinfunction "PGED_4") (pintype "passive"))
    )
  )
)
